# plugthroughckt.net
KiCad netlist of a schematic drawn in EAGLE
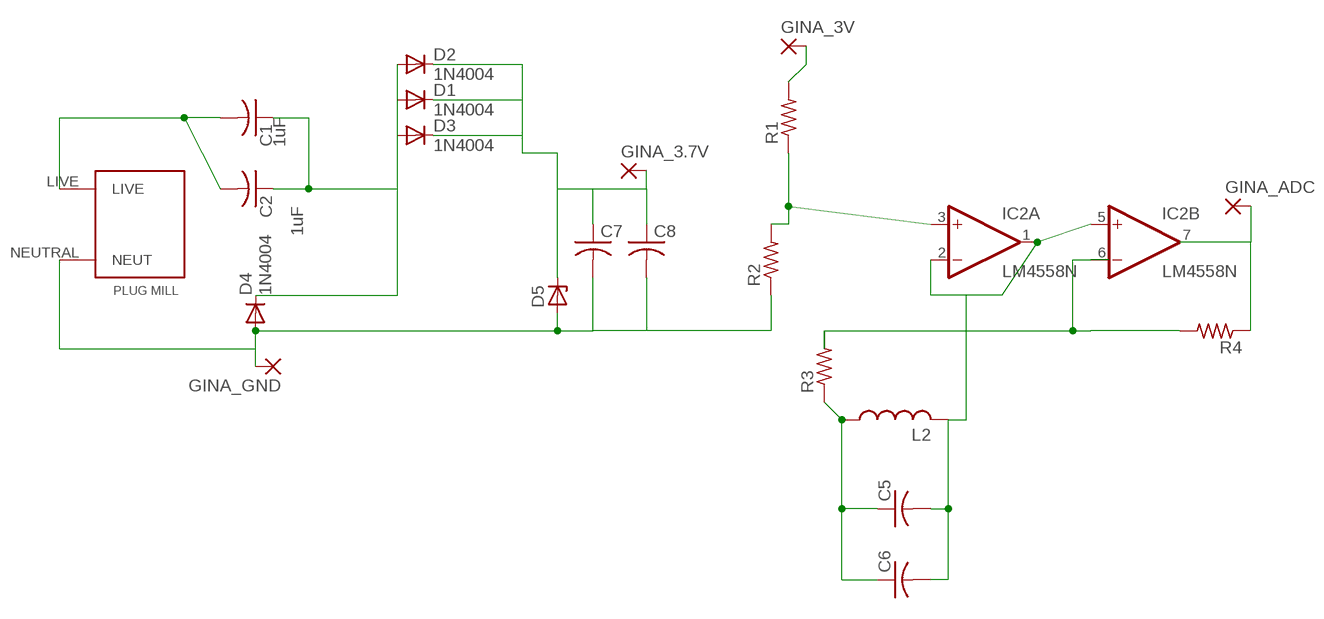
[diagram p0: schematic, sheet 1]

(export (version "E")
  (design (tool "Eeschema 10.0.6"))
  (components
    (comp (ref "C1")
      (value "C-US075-032X103")
      (footprint "eagle-import:C075-032X103")
      (fields (field (name "CAPACITANCE") "1uF"))
      (libsource (lib "eagle-import") (part "C-US075-032X103"))
    )
    (comp (ref "C2")
      (value "C-US075-032X103")
      (footprint "eagle-import:C075-032X103")
      (fields (field (name "CAPACITANCE") "1uF"))
      (libsource (lib "eagle-import") (part "C-US075-032X103"))
    )
    (comp (ref "C5")
      (value "C-US075-032X103")
      (footprint "eagle-import:C075-032X103")
      (libsource (lib "eagle-import") (part "resistor_C-US075-032X103"))
    )
    (comp (ref "C6")
      (value "C-US075-032X103")
      (footprint "eagle-import:C075-032X103")
      (libsource (lib "eagle-import") (part "resistor_C-US075-032X103"))
    )
    (comp (ref "C7")
      (value "C-US025-050X050")
      (footprint "eagle-import:C025-050X050")
      (libsource (lib "eagle-import") (part "C-US025-050X050"))
    )
    (comp (ref "C8")
      (value "C-US025-050X050")
      (footprint "eagle-import:C025-050X050")
      (libsource (lib "eagle-import") (part "C-US025-050X050"))
    )
    (comp (ref "D1")
      (value "1N4004")
      (footprint "eagle-import:DO41-10")
      (libsource (lib "eagle-import") (part "1N4004"))
    )
    (comp (ref "D2")
      (value "1N4004")
      (footprint "eagle-import:DO41-10")
      (libsource (lib "eagle-import") (part "1N4004"))
    )
    (comp (ref "D3")
      (value "1N4004")
      (footprint "eagle-import:DO41-10")
      (libsource (lib "eagle-import") (part "1N4004"))
    )
    (comp (ref "D4")
      (value "1N4004")
      (footprint "eagle-import:DO41-10")
      (libsource (lib "eagle-import") (part "1N4004"))
    )
    (comp (ref "D5")
      (value "ZENER-DIODEDO41Z10")
      (footprint "eagle-import:DO41Z10")
      (libsource (lib "eagle-import") (part "ZENER-DIODEDO41Z10"))
    )
    (comp (ref "GINA_3.7V")
      (value "3,81/1,4")
      (footprint "eagle-import:3,81_1,4")
      (libsource (lib "eagle-import") (part "3,81/1,4"))
    )
    (comp (ref "GINA_3V")
      (value "3,81/1,4")
      (footprint "eagle-import:3,81_1,4")
      (libsource (lib "eagle-import") (part "3,81/1,4"))
    )
    (comp (ref "GINA_ADC")
      (value "3,81/1,4")
      (footprint "eagle-import:3,81_1,4")
      (libsource (lib "eagle-import") (part "3,81/1,4"))
    )
    (comp (ref "GINA_GND")
      (value "3,81/1,4")
      (footprint "eagle-import:3,81_1,4")
      (libsource (lib "eagle-import") (part "3,81/1,4"))
    )
    (comp (ref "IC2")
      (value "LM4558N")
      (footprint "eagle-import:DIL08")
      (libsource (lib "eagle-import") (part "4558NLM"))
    )
    (comp (ref "L2")
      (value "L-US0207/5V")
      (footprint "eagle-import:0207_5V")
      (libsource (lib "eagle-import") (part "L-US0207/5V"))
    )
    (comp (ref "R1")
      (value "R-US_0207/10")
      (footprint "eagle-import:0207_10")
      (libsource (lib "eagle-import") (part "R-US_0207/10"))
    )
    (comp (ref "R2")
      (value "R-US_0207/10")
      (footprint "eagle-import:0207_10")
      (libsource (lib "eagle-import") (part "R-US_0207/10"))
    )
    (comp (ref "R3")
      (value "R-US_0207/10")
      (footprint "eagle-import:0207_10")
      (libsource (lib "eagle-import") (part "R-US_0207/10"))
    )
    (comp (ref "R4")
      (value "R-US_0207/10")
      (footprint "eagle-import:0207_10")
      (libsource (lib "eagle-import") (part "R-US_0207/10"))
    )
    (comp (ref "U$1")
      (value "PLUGMILL")
      (footprint "eagle-import:PLUGMILL")
      (libsource (lib "eagle-import") (part "PLUGMILL"))
    )
  )
  (nets
    (net (code "1") (name "Net-(C1-Pad1)") (class "Default")
      (node (ref "C1") (pin "1") (pinfunction "1_1") (pintype "passive"))
      (node (ref "C2") (pin "1") (pinfunction "1_1") (pintype "passive"))
      (node (ref "D1") (pin "A") (pinfunction "A_A") (pintype "passive"))
      (node (ref "D2") (pin "A") (pinfunction "A_A") (pintype "passive"))
      (node (ref "D3") (pin "A") (pinfunction "A_A") (pintype "passive"))
      (node (ref "D4") (pin "C") (pinfunction "C_C") (pintype "passive"))
    )
    (net (code "2") (name "Net-(C1-Pad2)") (class "Default")
      (node (ref "C1") (pin "2") (pinfunction "2_2") (pintype "passive"))
      (node (ref "C2") (pin "2") (pinfunction "2_2") (pintype "passive"))
      (node (ref "U$1") (pin "LIVE") (pinfunction "LIVE_LIVE") (pintype "bidirectional"))
    )
    (net (code "3") (name "Net-(C5-Pad1)") (class "Default")
      (node (ref "C5") (pin "1") (pinfunction "1_1") (pintype "passive"))
      (node (ref "C6") (pin "1") (pinfunction "1_1") (pintype "passive"))
      (node (ref "L2") (pin "1") (pinfunction "1_1") (pintype "passive"))
      (node (ref "R3") (pin "1") (pinfunction "1_1") (pintype "passive"))
    )
    (net (code "4") (name "Net-(GINA_3.7V-P)") (class "Default")
      (node (ref "C7") (pin "1") (pinfunction "1_1") (pintype "passive"))
      (node (ref "C8") (pin "1") (pinfunction "1_1") (pintype "passive"))
      (node (ref "D1") (pin "C") (pinfunction "C_C") (pintype "passive"))
      (node (ref "D2") (pin "C") (pinfunction "C_C") (pintype "passive"))
      (node (ref "D3") (pin "C") (pinfunction "C_C") (pintype "passive"))
      (node (ref "D5") (pin "C") (pinfunction "C_C") (pintype "passive"))
      (node (ref "GINA_3.7V") (pin "1") (pinfunction "P_1") (pintype "passive"))
    )
    (net (code "5") (name "Net-(GINA_3V-P)") (class "Default")
      (node (ref "GINA_3V") (pin "1") (pinfunction "P_1") (pintype "passive"))
      (node (ref "R1") (pin "2") (pinfunction "2_2") (pintype "passive"))
    )
    (net (code "6") (name "Net-(GINA_ADC-P)") (class "Default")
      (node (ref "GINA_ADC") (pin "1") (pinfunction "P_1") (pintype "passive"))
      (node (ref "IC2") (pin "7") (pinfunction "OUT_7") (pintype "output"))
      (node (ref "R4") (pin "1") (pinfunction "1_1") (pintype "passive"))
    )
    (net (code "7") (name "Net-(GINA_GND-P)") (class "Default")
      (node (ref "C7") (pin "2") (pinfunction "2_2") (pintype "passive"))
      (node (ref "C8") (pin "2") (pinfunction "2_2") (pintype "passive"))
      (node (ref "D4") (pin "A") (pinfunction "A_A") (pintype "passive"))
      (node (ref "D5") (pin "A") (pinfunction "A_A") (pintype "passive"))
      (node (ref "GINA_GND") (pin "1") (pinfunction "P_1") (pintype "passive"))
      (node (ref "R2") (pin "1") (pinfunction "1_1") (pintype "passive"))
      (node (ref "U$1") (pin "NEUTRAL") (pinfunction "NEUT_NEUTRAL") (pintype "bidirectional"))
    )
    (net (code "8") (name "Net-(IC2A-+IN)") (class "Default")
      (node (ref "IC2") (pin "3") (pinfunction "+IN_3") (pintype "input"))
      (node (ref "R1") (pin "1") (pinfunction "1_1") (pintype "passive"))
      (node (ref "R2") (pin "2") (pinfunction "2_2") (pintype "passive"))
    )
    (net (code "9") (name "Net-(IC2A--IN)") (class "Default")
      (node (ref "C5") (pin "2") (pinfunction "2_2") (pintype "passive"))
      (node (ref "C6") (pin "2") (pinfunction "2_2") (pintype "passive"))
      (node (ref "IC2") (pin "1") (pinfunction "OUT_1") (pintype "output"))
      (node (ref "IC2") (pin "2") (pinfunction "-IN_2") (pintype "input"))
      (node (ref "IC2") (pin "5") (pinfunction "+IN_5") (pintype "input"))
      (node (ref "L2") (pin "2") (pinfunction "2_2") (pintype "passive"))
    )
    (net (code "10") (name "Net-(IC2B--IN)") (class "Default")
      (node (ref "IC2") (pin "6") (pinfunction "-IN_6") (pintype "input"))
      (node (ref "R3") (pin "2") (pinfunction "2_2") (pintype "passive"))
      (node (ref "R4") (pin "2") (pinfunction "2_2") (pintype "passive"))
    )
  )
)
